# ESPkachu_V2.net
KiCad netlist of a schematic drawn in EAGLE
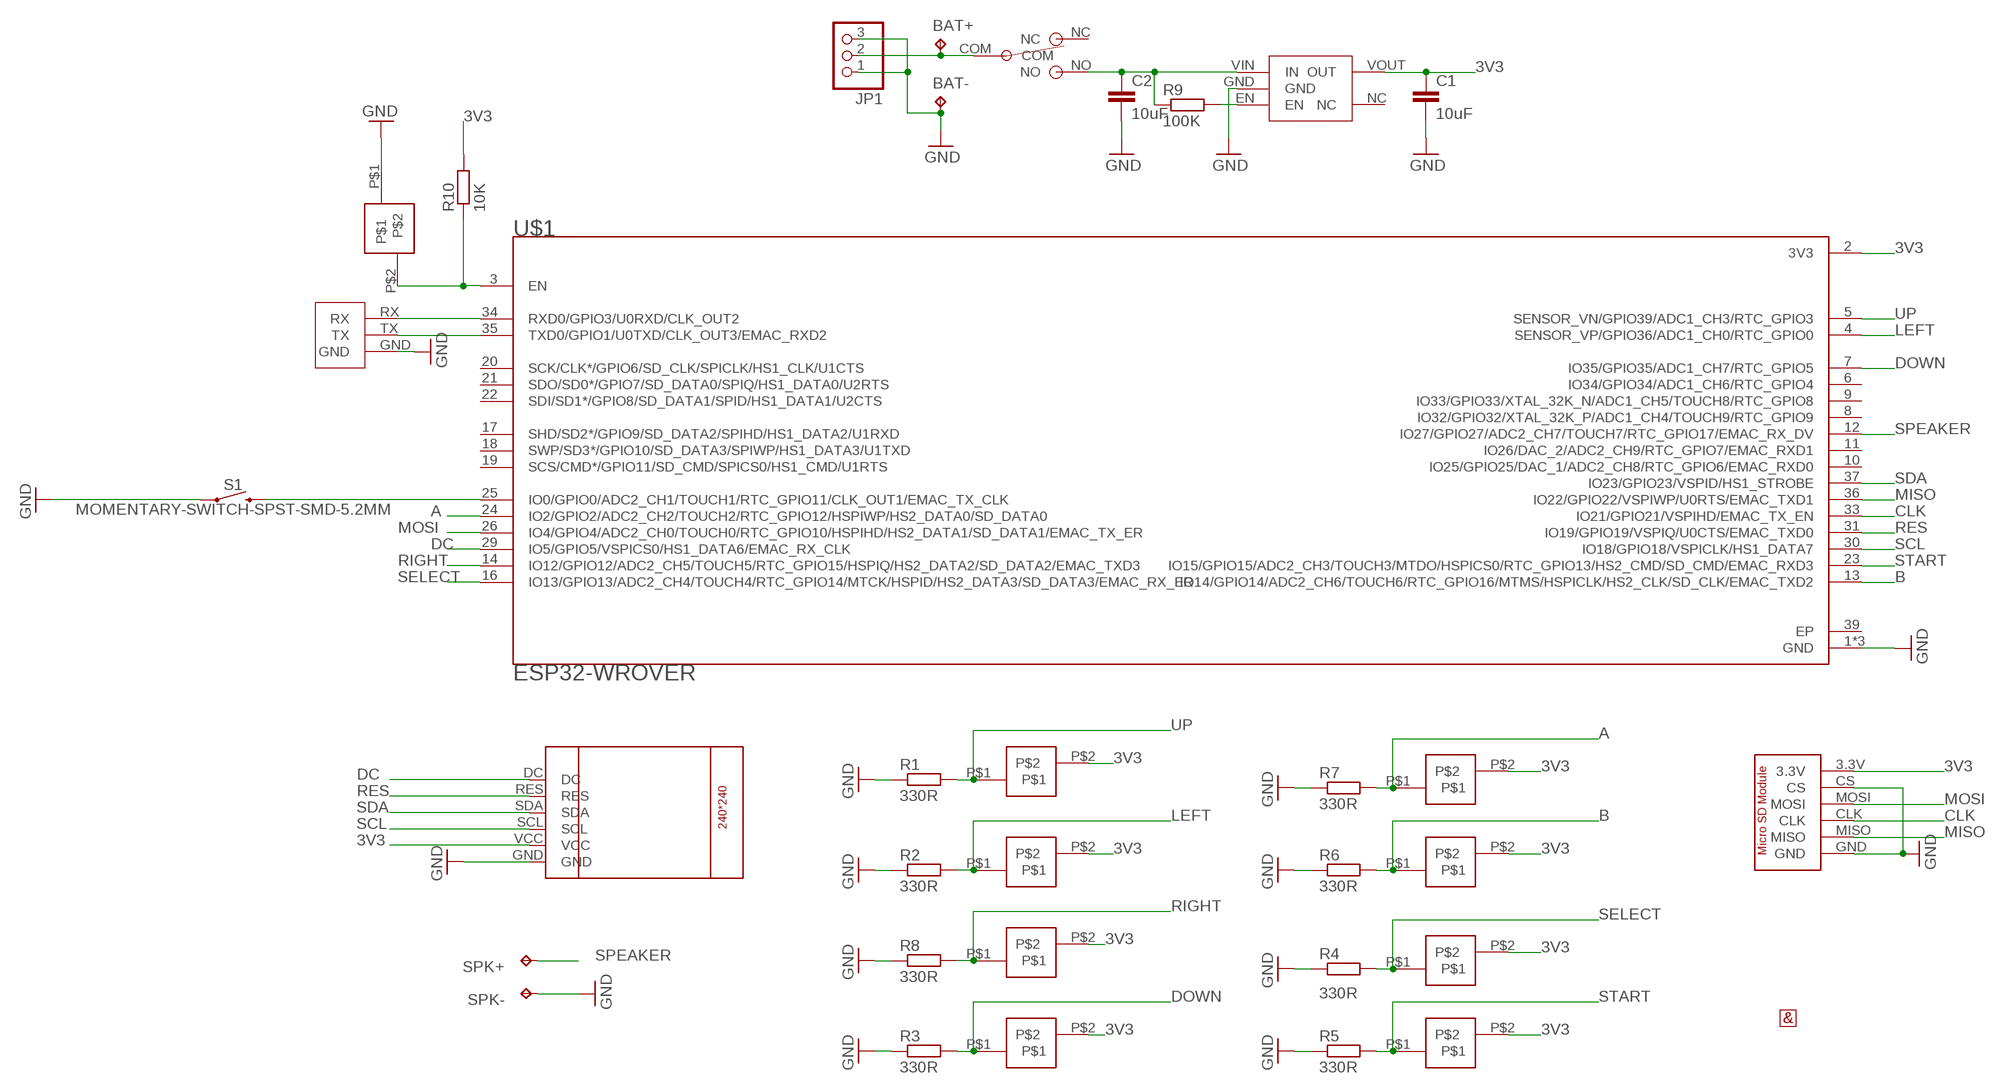
[diagram p0: schematic, sheet 1]

(export (version "E")
  (design (tool "Eeschema 10.0.6"))
  (components
    (comp (ref "A")
      (value "ESPKACHU-PAD")
      (footprint "eagle-import:ESPKACHU-PAD")
      (libsource (lib "eagle-import") (part "ESPKACHU-PAD"))
    )
    (comp (ref "B")
      (value "ESPKACHU-PAD")
      (footprint "eagle-import:ESPKACHU-PAD")
      (libsource (lib "eagle-import") (part "ESPKACHU-PAD"))
    )
    (comp (ref "BAT+")
      (value "TPTP20R")
      (footprint "eagle-import:TP20R")
      (libsource (lib "eagle-import") (part "TPTP20R"))
    )
    (comp (ref "BAT-")
      (value "TPTP20R")
      (footprint "eagle-import:TP20R")
      (libsource (lib "eagle-import") (part "TPTP20R"))
    )
    (comp (ref "C1")
      (value "10uF")
      (footprint "eagle-import:C0805")
      (libsource (lib "eagle-import") (part "C-EUC0805"))
    )
    (comp (ref "C2")
      (value "10uF")
      (footprint "eagle-import:C0805")
      (libsource (lib "eagle-import") (part "C-EUC0805"))
    )
    (comp (ref "DOWN")
      (value "ESPKACHU-PAD")
      (footprint "eagle-import:ESPKACHU-PAD")
      (libsource (lib "eagle-import") (part "ESPKACHU-PAD"))
    )
    (comp (ref "JP1")
      (value "PINHD-1X03_2.54-S")
      (footprint "eagle-import:1X03-S")
      (libsource (lib "eagle-import") (part "PINHD-1X03_2.54-S"))
    )
    (comp (ref "LEFT")
      (value "ESPKACHU-PAD")
      (footprint "eagle-import:ESPKACHU-PAD")
      (libsource (lib "eagle-import") (part "ESPKACHU-PAD"))
    )
    (comp (ref "R1")
      (value "330R")
      (footprint "eagle-import:M0805")
      (libsource (lib "eagle-import") (part "R-EU_M0805"))
    )
    (comp (ref "R2")
      (value "330R")
      (footprint "eagle-import:M0805")
      (libsource (lib "eagle-import") (part "R-EU_M0805"))
    )
    (comp (ref "R3")
      (value "330R")
      (footprint "eagle-import:M0805")
      (libsource (lib "eagle-import") (part "R-EU_M0805"))
    )
    (comp (ref "R4")
      (value "330R")
      (footprint "eagle-import:M0805")
      (libsource (lib "eagle-import") (part "R-EU_M0805"))
    )
    (comp (ref "R5")
      (value "330R")
      (footprint "eagle-import:M0805")
      (libsource (lib "eagle-import") (part "R-EU_M0805"))
    )
    (comp (ref "R6")
      (value "330R")
      (footprint "eagle-import:M0805")
      (libsource (lib "eagle-import") (part "R-EU_M0805"))
    )
    (comp (ref "R7")
      (value "330R")
      (footprint "eagle-import:M0805")
      (libsource (lib "eagle-import") (part "R-EU_M0805"))
    )
    (comp (ref "R8")
      (value "330R")
      (footprint "eagle-import:M0805")
      (libsource (lib "eagle-import") (part "R-EU_M0805"))
    )
    (comp (ref "R9")
      (value "100K")
      (footprint "eagle-import:M0805")
      (libsource (lib "eagle-import") (part "R-EU_M0805"))
    )
    (comp (ref "R10")
      (value "10K")
      (footprint "eagle-import:M0805")
      (libsource (lib "eagle-import") (part "R-EU_M0805"))
    )
    (comp (ref "RESET")
      (value "ESPKACHU-PAD")
      (footprint "eagle-import:ESPKACHU-PAD")
      (libsource (lib "eagle-import") (part "ESPKACHU-PAD"))
    )
    (comp (ref "RIGHT")
      (value "ESPKACHU-PAD")
      (footprint "eagle-import:ESPKACHU-PAD")
      (libsource (lib "eagle-import") (part "ESPKACHU-PAD"))
    )
    (comp (ref "S1")
      (value "MOMENTARY-SWITCH-SPST-SMD-5.2MM")
      (footprint "eagle-import:TACTILE_SWITCH_SMD_5.2MM")
      (libsource (lib "eagle-import") (part "MOMENTARY-SWITCH-SPST-SMD-5.2MM"))
    )
    (comp (ref "SELECT")
      (value "ESPKACHU-PAD")
      (footprint "eagle-import:ESPKACHU-PAD")
      (libsource (lib "eagle-import") (part "ESPKACHU-PAD"))
    )
    (comp (ref "SPK+")
      (value "TPTP20R")
      (footprint "eagle-import:TP20R")
      (libsource (lib "eagle-import") (part "TPTP20R"))
    )
    (comp (ref "SPK-")
      (value "TPTP20R")
      (footprint "eagle-import:TP20R")
      (libsource (lib "eagle-import") (part "TPTP20R"))
    )
    (comp (ref "START")
      (value "ESPKACHU-PAD")
      (footprint "eagle-import:ESPKACHU-PAD")
      (libsource (lib "eagle-import") (part "ESPKACHU-PAD"))
    )
    (comp (ref "U$1")
      (value "ESP32-WROVER")
      (footprint "eagle-import:XCVR-ESP32-WROVER")
      (libsource (lib "eagle-import") (part "ESP32-WROVER"))
    )
    (comp (ref "U$2")
      (value "LCD-ST7789-1.3INCH")
      (footprint "eagle-import:LCD-ST7789-1.3INCH")
      (libsource (lib "eagle-import") (part "LCD-ST7789-1.3INCH"))
    )
    (comp (ref "U$3")
      (value "ESPRESSO-MICROSD-MODULE")
      (footprint "eagle-import:ESPRESSO-MICROSD-MODULE")
      (libsource (lib "eagle-import") (part "ESPRESSO-MICROSD-MODULE"))
    )
    (comp (ref "U$4")
      (value "SS12D00-SWITCH")
      (footprint "eagle-import:SS12D00-SWITCH")
      (libsource (lib "eagle-import") (part "SS12D00-SWITCH"))
    )
    (comp (ref "U$5")
      (value "AMP-HALF")
      (footprint "eagle-import:AMP-HALF")
      (libsource (lib "eagle-import") (part "AMP-HALF"))
    )
    (comp (ref "U$6")
      (value "AP2112-REGULATOR")
      (footprint "eagle-import:SOT25")
      (libsource (lib "eagle-import") (part "AP2112-REGULATOR"))
    )
    (comp (ref "U$7")
      (value "ESPKACHU-UART")
      (footprint "eagle-import:ESPKACHU-UART")
      (libsource (lib "eagle-import") (part "ESPKACHU-UART"))
    )
    (comp (ref "UP")
      (value "ESPKACHU-PAD")
      (footprint "eagle-import:ESPKACHU-PAD")
      (libsource (lib "eagle-import") (part "ESPKACHU-PAD"))
    )
  )
  (nets
    (net (code "1") (name "/3V3") (class "Default")
      (node (ref "A") (pin "P$2") (pinfunction "P$2_P$2") (pintype "bidirectional"))
      (node (ref "B") (pin "P$2") (pinfunction "P$2_P$2") (pintype "bidirectional"))
      (node (ref "C1") (pin "1") (pinfunction "1_1") (pintype "passive"))
      (node (ref "DOWN") (pin "P$2") (pinfunction "P$2_P$2") (pintype "bidirectional"))
      (node (ref "LEFT") (pin "P$2") (pinfunction "P$2_P$2") (pintype "bidirectional"))
      (node (ref "R10") (pin "2") (pinfunction "2_2") (pintype "passive"))
      (node (ref "RIGHT") (pin "P$2") (pinfunction "P$2_P$2") (pintype "bidirectional"))
      (node (ref "SELECT") (pin "P$2") (pinfunction "P$2_P$2") (pintype "bidirectional"))
      (node (ref "START") (pin "P$2") (pinfunction "P$2_P$2") (pintype "bidirectional"))
      (node (ref "U$1") (pin "2") (pinfunction "3V3_2") (pintype "power_in"))
      (node (ref "U$2") (pin "VCC") (pinfunction "VCC_VCC") (pintype "bidirectional"))
      (node (ref "U$3") (pin "3.3V") (pinfunction "3.3V_3.3V") (pintype "bidirectional"))
      (node (ref "U$6") (pin "VOUT") (pinfunction "OUT_VOUT") (pintype "bidirectional"))
      (node (ref "UP") (pin "P$2") (pinfunction "P$2_P$2") (pintype "bidirectional"))
    )
    (net (code "2") (name "/A") (class "Default")
      (node (ref "A") (pin "P$1") (pinfunction "P$1_P$1") (pintype "bidirectional"))
      (node (ref "R7") (pin "2") (pinfunction "2_2") (pintype "passive"))
      (node (ref "U$1") (pin "24") (pinfunction "IO2/GPIO2/ADC2_CH2/TOUCH2/RTC_GPIO12/HSPIWP/HS2_DATA0/SD_DATA0_24") (pintype "bidirectional"))
    )
    (net (code "3") (name "/B") (class "Default")
      (node (ref "B") (pin "P$1") (pinfunction "P$1_P$1") (pintype "bidirectional"))
      (node (ref "R6") (pin "2") (pinfunction "2_2") (pintype "passive"))
      (node (ref "U$1") (pin "13") (pinfunction "IO14/GPIO14/ADC2_CH6/TOUCH6/RTC_GPIO16/MTMS/HSPICLK/HS2_CLK/SD_CLK/EMAC_TXD2_13") (pintype "bidirectional"))
    )
    (net (code "4") (name "/CLK") (class "Default")
      (node (ref "U$1") (pin "33") (pinfunction "IO21/GPIO21/VSPIHD/EMAC_TX_EN_33") (pintype "bidirectional"))
      (node (ref "U$3") (pin "CLK") (pinfunction "CLK_CLK") (pintype "bidirectional"))
    )
    (net (code "5") (name "/DC") (class "Default")
      (node (ref "U$1") (pin "29") (pinfunction "IO5/GPIO5/VSPICS0/HS1_DATA6/EMAC_RX_CLK_29") (pintype "bidirectional"))
      (node (ref "U$2") (pin "DC") (pinfunction "DC_DC") (pintype "bidirectional"))
    )
    (net (code "6") (name "/DOWN") (class "Default")
      (node (ref "DOWN") (pin "P$1") (pinfunction "P$1_P$1") (pintype "bidirectional"))
      (node (ref "R3") (pin "2") (pinfunction "2_2") (pintype "passive"))
      (node (ref "U$1") (pin "7") (pinfunction "IO35/GPIO35/ADC1_CH7/RTC_GPIO5_7") (pintype "bidirectional"))
    )
    (net (code "7") (name "/EP") (class "Default")
      (node (ref "U$1") (pin "39") (pinfunction "EP_39") (pintype "power_in"))
    )
    (net (code "8") (name "/LEFT") (class "Default")
      (node (ref "LEFT") (pin "P$1") (pinfunction "P$1_P$1") (pintype "bidirectional"))
      (node (ref "R2") (pin "2") (pinfunction "2_2") (pintype "passive"))
      (node (ref "U$1") (pin "4") (pinfunction "SENSOR_VP/GPIO36/ADC1_CH0/RTC_GPIO0_4") (pintype "bidirectional"))
    )
    (net (code "9") (name "/MISO") (class "Default")
      (node (ref "U$1") (pin "36") (pinfunction "IO22/GPIO22/VSPIWP/U0RTS/EMAC_TXD1_36") (pintype "bidirectional"))
      (node (ref "U$3") (pin "MISO") (pinfunction "MISO_MISO") (pintype "bidirectional"))
    )
    (net (code "10") (name "/MOSI") (class "Default")
      (node (ref "U$1") (pin "26") (pinfunction "IO4/GPIO4/ADC2_CH0/TOUCH0/RTC_GPIO10/HSPIHD/HS2_DATA1/SD_DATA1/EMAC_TX_ER_26") (pintype "bidirectional"))
      (node (ref "U$3") (pin "MOSI") (pinfunction "MOSI_MOSI") (pintype "bidirectional"))
    )
    (net (code "11") (name "/RES") (class "Default")
      (node (ref "U$1") (pin "31") (pinfunction "IO19/GPIO19/VSPIQ/U0CTS/EMAC_TXD0_31") (pintype "bidirectional"))
      (node (ref "U$2") (pin "RES") (pinfunction "RES_RES") (pintype "bidirectional"))
    )
    (net (code "12") (name "/RIGHT") (class "Default")
      (node (ref "R8") (pin "2") (pinfunction "2_2") (pintype "passive"))
      (node (ref "RIGHT") (pin "P$1") (pinfunction "P$1_P$1") (pintype "bidirectional"))
      (node (ref "U$1") (pin "14") (pinfunction "IO12/GPIO12/ADC2_CH5/TOUCH5/RTC_GPIO15/HSPIQ/HS2_DATA2/SD_DATA2/EMAC_TXD3_14") (pintype "bidirectional"))
    )
    (net (code "13") (name "/SCL") (class "Default")
      (node (ref "U$1") (pin "30") (pinfunction "IO18/GPIO18/VSPICLK/HS1_DATA7_30") (pintype "bidirectional"))
      (node (ref "U$2") (pin "SCL") (pinfunction "SCL_SCL") (pintype "bidirectional"))
    )
    (net (code "14") (name "/SDA") (class "Default")
      (node (ref "U$1") (pin "37") (pinfunction "IO23/GPIO23/VSPID/HS1_STROBE_37") (pintype "bidirectional"))
      (node (ref "U$2") (pin "SDA") (pinfunction "SDA_SDA") (pintype "bidirectional"))
    )
    (net (code "15") (name "/SELECT") (class "Default")
      (node (ref "R4") (pin "2") (pinfunction "2_2") (pintype "passive"))
      (node (ref "SELECT") (pin "P$1") (pinfunction "P$1_P$1") (pintype "bidirectional"))
      (node (ref "U$1") (pin "16") (pinfunction "IO13/GPIO13/ADC2_CH4/TOUCH4/RTC_GPIO14/MTCK/HSPID/HS2_DATA3/SD_DATA3/EMAC_RX_ER_16") (pintype "bidirectional"))
    )
    (net (code "16") (name "/SPEAKER") (class "Default")
      (node (ref "SPK+") (pin "TP") (pinfunction "TP_TP") (pintype "input"))
      (node (ref "U$1") (pin "12") (pinfunction "IO27/GPIO27/ADC2_CH7/TOUCH7/RTC_GPIO17/EMAC_RX_DV_12") (pintype "bidirectional"))
    )
    (net (code "17") (name "/START") (class "Default")
      (node (ref "R5") (pin "2") (pinfunction "2_2") (pintype "passive"))
      (node (ref "START") (pin "P$1") (pinfunction "P$1_P$1") (pintype "bidirectional"))
      (node (ref "U$1") (pin "23") (pinfunction "IO15/GPIO15/ADC2_CH3/TOUCH3/MTDO/HSPICS0/RTC_GPIO13/HS2_CMD/SD_CMD/EMAC_RXD3_23") (pintype "bidirectional"))
    )
    (net (code "18") (name "/UP") (class "Default")
      (node (ref "R1") (pin "2") (pinfunction "2_2") (pintype "passive"))
      (node (ref "U$1") (pin "5") (pinfunction "SENSOR_VN/GPIO39/ADC1_CH3/RTC_GPIO3_5") (pintype "bidirectional"))
      (node (ref "UP") (pin "P$1") (pinfunction "P$1_P$1") (pintype "bidirectional"))
    )
    (net (code "19") (name "GND") (class "Default")
      (node (ref "BAT-") (pin "TP") (pinfunction "TP_TP") (pintype "input"))
      (node (ref "C1") (pin "2") (pinfunction "2_2") (pintype "passive"))
      (node (ref "C2") (pin "2") (pinfunction "2_2") (pintype "passive"))
      (node (ref "JP1") (pin "1") (pinfunction "1_1") (pintype "passive"))
      (node (ref "JP1") (pin "3") (pinfunction "3_3") (pintype "passive"))
      (node (ref "R1") (pin "1") (pinfunction "1_1") (pintype "passive"))
      (node (ref "R2") (pin "1") (pinfunction "1_1") (pintype "passive"))
      (node (ref "R3") (pin "1") (pinfunction "1_1") (pintype "passive"))
      (node (ref "R4") (pin "1") (pinfunction "1_1") (pintype "passive"))
      (node (ref "R5") (pin "1") (pinfunction "1_1") (pintype "passive"))
      (node (ref "R6") (pin "1") (pinfunction "1_1") (pintype "passive"))
      (node (ref "R7") (pin "1") (pinfunction "1_1") (pintype "passive"))
      (node (ref "R8") (pin "1") (pinfunction "1_1") (pintype "passive"))
      (node (ref "RESET") (pin "P$1") (pinfunction "P$1_P$1") (pintype "bidirectional"))
      (node (ref "S1") (pin "1") (pinfunction "1_1") (pintype "passive"))
      (node (ref "S1") (pin "2") (pinfunction "1_2") (pintype "passive"))
      (node (ref "SPK-") (pin "TP") (pinfunction "TP_TP") (pintype "input"))
      (node (ref "U$1") (pin "1") (pinfunction "GND_1") (pintype "power_in"))
      (node (ref "U$1") (pin "15") (pinfunction "GND_15") (pintype "power_in"))
      (node (ref "U$1") (pin "38") (pinfunction "GND_38") (pintype "power_in"))
      (node (ref "U$2") (pin "GND") (pinfunction "GND_GND") (pintype "bidirectional"))
      (node (ref "U$3") (pin "CS") (pinfunction "CS_CS") (pintype "bidirectional"))
      (node (ref "U$3") (pin "GND") (pinfunction "GND_GND") (pintype "bidirectional"))
      (node (ref "U$6") (pin "GND") (pinfunction "GND_GND") (pintype "bidirectional"))
      (node (ref "U$7") (pin "GND") (pinfunction "GND_GND") (pintype "bidirectional"))
    )
    (net (code "20") (name "Net-(BAT+-PadTP)") (class "Default")
      (node (ref "BAT+") (pin "TP") (pinfunction "TP_TP") (pintype "input"))
      (node (ref "JP1") (pin "2") (pinfunction "2_2") (pintype "passive"))
      (node (ref "U$4") (pin "COM") (pinfunction "COM_COM") (pintype "bidirectional"))
    )
    (net (code "21") (name "Net-(R9-Pad2)") (class "Default")
      (node (ref "R9") (pin "2") (pinfunction "2_2") (pintype "passive"))
      (node (ref "U$6") (pin "EN") (pinfunction "EN_EN") (pintype "bidirectional"))
    )
    (net (code "22") (name "Net-(U$1-EN)") (class "Default")
      (node (ref "R10") (pin "1") (pinfunction "1_1") (pintype "passive"))
      (node (ref "RESET") (pin "P$2") (pinfunction "P$2_P$2") (pintype "bidirectional"))
      (node (ref "U$1") (pin "3") (pinfunction "EN_3") (pintype "input"))
    )
    (net (code "23") (name "Net-(U$1-IO0{slash}GPIO0{slash}ADC2_CH1{slash}TOUCH1{slash}RTC_GPIO11{slash}CLK_OUT1{slash}EMAC_TX_CLK)") (class "Default")
      (node (ref "S1") (pin "3") (pinfunction "2_3") (pintype "passive"))
      (node (ref "S1") (pin "4") (pinfunction "2_4") (pintype "passive"))
      (node (ref "U$1") (pin "25") (pinfunction "IO0/GPIO0/ADC2_CH1/TOUCH1/RTC_GPIO11/CLK_OUT1/EMAC_TX_CLK_25") (pintype "bidirectional"))
    )
    (net (code "24") (name "Net-(U$1-RXD0{slash}GPIO3{slash}U0RXD{slash}CLK_OUT2)") (class "Default")
      (node (ref "U$1") (pin "34") (pinfunction "RXD0/GPIO3/U0RXD/CLK_OUT2_34") (pintype "bidirectional"))
      (node (ref "U$7") (pin "RX") (pinfunction "RX_RX") (pintype "bidirectional"))
    )
    (net (code "25") (name "Net-(U$1-TXD0{slash}GPIO1{slash}U0TXD{slash}CLK_OUT3{slash}EMAC_RXD2)") (class "Default")
      (node (ref "U$1") (pin "35") (pinfunction "TXD0/GPIO1/U0TXD/CLK_OUT3/EMAC_RXD2_35") (pintype "bidirectional"))
      (node (ref "U$7") (pin "TX") (pinfunction "TX_TX") (pintype "bidirectional"))
    )
    (net (code "26") (name "Net-(U$6-IN)") (class "Default")
      (node (ref "C2") (pin "1") (pinfunction "1_1") (pintype "passive"))
      (node (ref "R9") (pin "1") (pinfunction "1_1") (pintype "passive"))
      (node (ref "U$4") (pin "NO") (pinfunction "NO_NO") (pintype "bidirectional"))
      (node (ref "U$6") (pin "VIN") (pinfunction "IN_VIN") (pintype "bidirectional"))
    )
    (net (code "27") (name "unconnected-(U$1-IO25{slash}GPIO25{slash}DAC_1{slash}ADC2_CH8{slash}RTC_GPIO6{slash}EMAC_RXD0-Pad10)") (class "Default")
      (node (ref "U$1") (pin "10") (pinfunction "IO25/GPIO25/DAC_1/ADC2_CH8/RTC_GPIO6/EMAC_RXD0_10") (pintype "bidirectional"))
    )
    (net (code "28") (name "unconnected-(U$1-IO26{slash}DAC_2{slash}ADC2_CH9{slash}RTC_GPIO7{slash}EMAC_RXD1-Pad11)") (class "Default")
      (node (ref "U$1") (pin "11") (pinfunction "IO26/DAC_2/ADC2_CH9/RTC_GPIO7/EMAC_RXD1_11") (pintype "bidirectional"))
    )
    (net (code "29") (name "unconnected-(U$1-IO32{slash}GPIO32{slash}XTAL_32K_P{slash}ADC1_CH4{slash}TOUCH9{slash}RTC_GPIO9-Pad8)") (class "Default")
      (node (ref "U$1") (pin "8") (pinfunction "IO32/GPIO32/XTAL_32K_P/ADC1_CH4/TOUCH9/RTC_GPIO9_8") (pintype "bidirectional"))
    )
    (net (code "30") (name "unconnected-(U$1-IO33{slash}GPIO33{slash}XTAL_32K_N{slash}ADC1_CH5{slash}TOUCH8{slash}RTC_GPIO8-Pad9)") (class "Default")
      (node (ref "U$1") (pin "9") (pinfunction "IO33/GPIO33/XTAL_32K_N/ADC1_CH5/TOUCH8/RTC_GPIO8_9") (pintype "bidirectional"))
    )
    (net (code "31") (name "unconnected-(U$1-IO34{slash}GPIO34{slash}ADC1_CH6{slash}RTC_GPIO4-Pad6)") (class "Default")
      (node (ref "U$1") (pin "6") (pinfunction "IO34/GPIO34/ADC1_CH6/RTC_GPIO4_6") (pintype "bidirectional"))
    )
    (net (code "32") (name "unconnected-(U$1-SCK{slash}CLK*{slash}GPIO6{slash}SD_CLK{slash}SPICLK{slash}HS1_CLK{slash}U1CTS-Pad20)") (class "Default")
      (node (ref "U$1") (pin "20") (pinfunction "SCK/CLK*/GPIO6/SD_CLK/SPICLK/HS1_CLK/U1CTS_20") (pintype "bidirectional"))
    )
    (net (code "33") (name "unconnected-(U$1-SCS{slash}CMD*{slash}GPIO11{slash}SD_CMD{slash}SPICS0{slash}HS1_CMD{slash}U1RTS-Pad19)") (class "Default")
      (node (ref "U$1") (pin "19") (pinfunction "SCS/CMD*/GPIO11/SD_CMD/SPICS0/HS1_CMD/U1RTS_19") (pintype "bidirectional"))
    )
    (net (code "34") (name "unconnected-(U$1-SDI{slash}SD1*{slash}GPIO8{slash}SD_DATA1{slash}SPID{slash}HS1_DATA1{slash}U2CTS-Pad22)") (class "Default")
      (node (ref "U$1") (pin "22") (pinfunction "SDI/SD1*/GPIO8/SD_DATA1/SPID/HS1_DATA1/U2CTS_22") (pintype "bidirectional"))
    )
    (net (code "35") (name "unconnected-(U$1-SDO{slash}SD0*{slash}GPIO7{slash}SD_DATA0{slash}SPIQ{slash}HS1_DATA0{slash}U2RTS-Pad21)") (class "Default")
      (node (ref "U$1") (pin "21") (pinfunction "SDO/SD0*/GPIO7/SD_DATA0/SPIQ/HS1_DATA0/U2RTS_21") (pintype "bidirectional"))
    )
    (net (code "36") (name "unconnected-(U$1-SHD{slash}SD2*{slash}GPIO9{slash}SD_DATA2{slash}SPIHD{slash}HS1_DATA2{slash}U1RXD-Pad17)") (class "Default")
      (node (ref "U$1") (pin "17") (pinfunction "SHD/SD2*/GPIO9/SD_DATA2/SPIHD/HS1_DATA2/U1RXD_17") (pintype "bidirectional"))
    )
    (net (code "37") (name "unconnected-(U$1-SWP{slash}SD3*{slash}GPIO10{slash}SD_DATA3{slash}SPIWP{slash}HS1_DATA3{slash}U1TXD-Pad18)") (class "Default")
      (node (ref "U$1") (pin "18") (pinfunction "SWP/SD3*/GPIO10/SD_DATA3/SPIWP/HS1_DATA3/U1TXD_18") (pintype "bidirectional"))
    )
    (net (code "38") (name "unconnected-(U$4-PadNC)") (class "Default")
      (node (ref "U$4") (pin "NC") (pinfunction "NC_NC") (pintype "bidirectional"))
    )
    (net (code "39") (name "unconnected-(U$6-PadNC)") (class "Default")
      (node (ref "U$6") (pin "NC") (pinfunction "NC_NC") (pintype "bidirectional"))
    )
  )
)
